# ATmega328_-_nRF24L01p_test_board.net
KiCad netlist of a schematic drawn in EAGLE
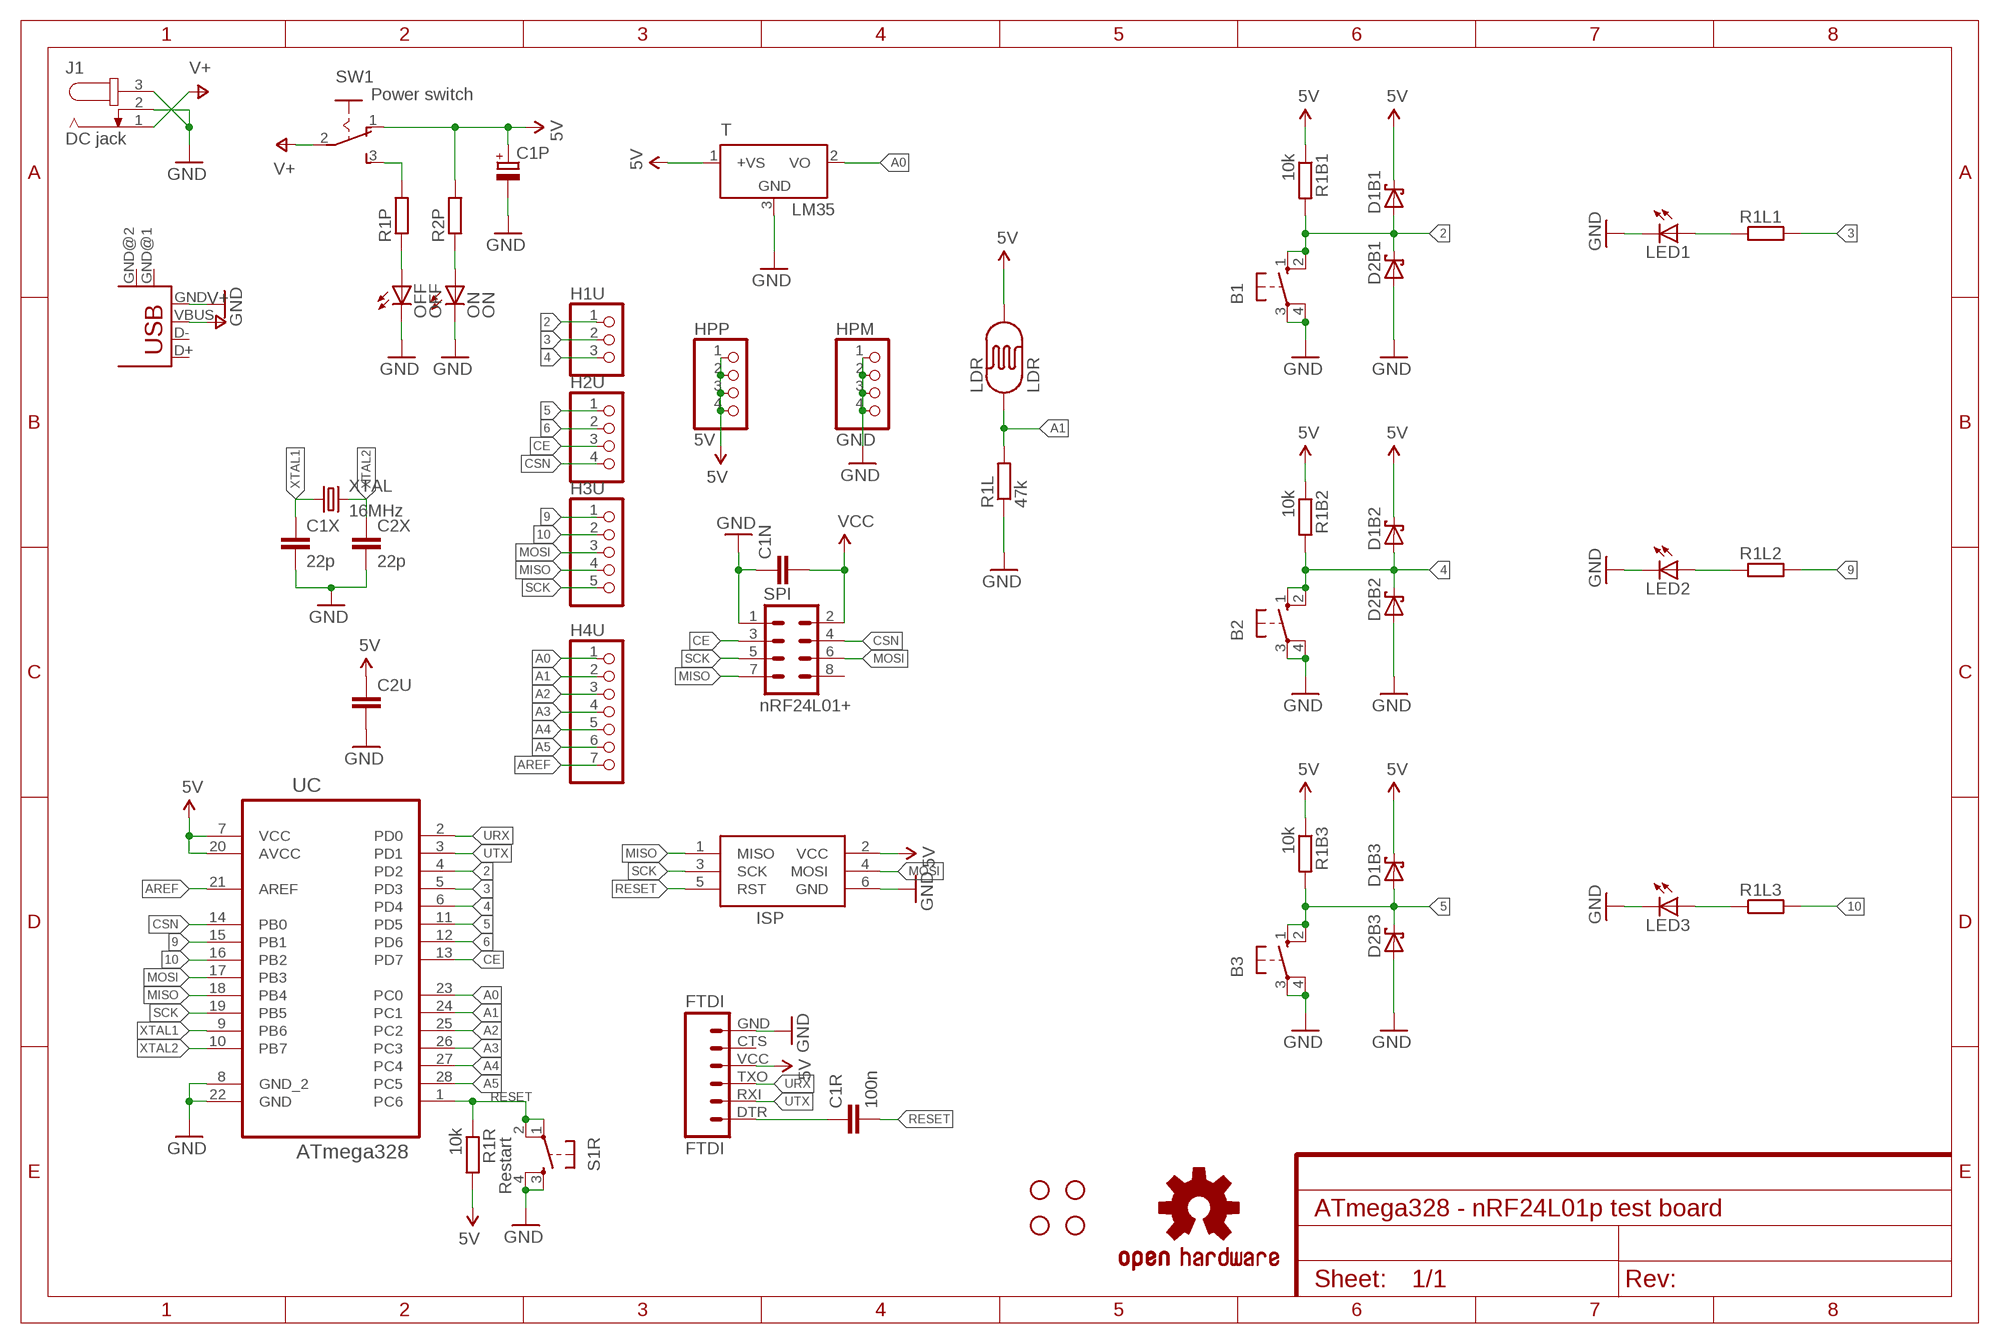
[diagram p0: schematic, sheet 1]

(export (version "E")
  (design (tool "Eeschema 10.0.6"))
  (components
    (comp (ref "B1")
      (value "40-XX")
      (footprint "eagle-import:B3F-40XX")
      (fields (field (name "MF") "OMRON COMPONENTS USA") (field (name "MPN") "B3F-4000"))
      (libsource (lib "eagle-import") (part "40-XX"))
    )
    (comp (ref "B2")
      (value "40-XX")
      (footprint "eagle-import:B3F-40XX")
      (fields (field (name "MF") "OMRON COMPONENTS USA") (field (name "MPN") "B3F-4000"))
      (libsource (lib "eagle-import") (part "40-XX"))
    )
    (comp (ref "B3")
      (value "40-XX")
      (footprint "eagle-import:B3F-40XX")
      (fields (field (name "MF") "OMRON COMPONENTS USA") (field (name "MPN") "B3F-4000"))
      (libsource (lib "eagle-import") (part "40-XX"))
    )
    (comp (ref "C1N")
      (value "C-EU050-025X075")
      (footprint "eagle-import:C050-025X075")
      (libsource (lib "eagle-import") (part "resistor_C-EU050-025X075"))
    )
    (comp (ref "C1P")
      (value "CPOL-EUE5-8.5")
      (footprint "eagle-import:E5-8,5")
      (libsource (lib "eagle-import") (part "CPOL-EUE5-8.5"))
    )
    (comp (ref "C1R")
      (value "100n")
      (footprint "eagle-import:C050-025X075")
      (libsource (lib "eagle-import") (part "resistor_C-EU050-025X075"))
    )
    (comp (ref "C1X")
      (value "22p")
      (footprint "eagle-import:C025-025X050")
      (libsource (lib "eagle-import") (part "resistor_C-EU025-025X050"))
    )
    (comp (ref "C2U")
      (value "C-EU050-055X075")
      (footprint "eagle-import:C050-055X075")
      (libsource (lib "eagle-import") (part "C-EU050-055X075"))
    )
    (comp (ref "C2X")
      (value "22p")
      (footprint "eagle-import:C025-025X050")
      (libsource (lib "eagle-import") (part "resistor_C-EU025-025X050"))
    )
    (comp (ref "D1B1")
      (value "SCHOTTKY-DIODEDO41-7")
      (footprint "eagle-import:DO41-7")
      (libsource (lib "eagle-import") (part "SCHOTTKY-DIODEDO41-7"))
    )
    (comp (ref "D1B2")
      (value "SCHOTTKY-DIODEDO41-7")
      (footprint "eagle-import:DO41-7")
      (libsource (lib "eagle-import") (part "SCHOTTKY-DIODEDO41-7"))
    )
    (comp (ref "D1B3")
      (value "SCHOTTKY-DIODEDO41-7")
      (footprint "eagle-import:DO41-7")
      (libsource (lib "eagle-import") (part "SCHOTTKY-DIODEDO41-7"))
    )
    (comp (ref "D2B1")
      (value "SCHOTTKY-DIODEDO41-7")
      (footprint "eagle-import:DO41-7")
      (libsource (lib "eagle-import") (part "SCHOTTKY-DIODEDO41-7"))
    )
    (comp (ref "D2B2")
      (value "SCHOTTKY-DIODEDO41-7")
      (footprint "eagle-import:DO41-7")
      (libsource (lib "eagle-import") (part "SCHOTTKY-DIODEDO41-7"))
    )
    (comp (ref "D2B3")
      (value "SCHOTTKY-DIODEDO41-7")
      (footprint "eagle-import:DO41-7")
      (libsource (lib "eagle-import") (part "SCHOTTKY-DIODEDO41-7"))
    )
    (comp (ref "FTDI")
      (value "FTDI")
      (footprint "eagle-import:FTDI_BASIC")
      (libsource (lib "eagle-import") (part "FTDI_BASICPTH"))
    )
    (comp (ref "H1")
      (value "STAND-OFF")
      (footprint "eagle-import:STAND-OFF")
      (libsource (lib "eagle-import") (part "STAND-OFF"))
    )
    (comp (ref "H1U")
      (value "PINHD-1X3")
      (footprint "eagle-import:1X03")
      (libsource (lib "eagle-import") (part "PINHD-1X3"))
    )
    (comp (ref "H2")
      (value "STAND-OFF")
      (footprint "eagle-import:STAND-OFF")
      (libsource (lib "eagle-import") (part "STAND-OFF"))
    )
    (comp (ref "H2U")
      (value "PINHD-1X4")
      (footprint "eagle-import:1X04")
      (libsource (lib "eagle-import") (part "PINHD-1X4"))
    )
    (comp (ref "H3")
      (value "STAND-OFF")
      (footprint "eagle-import:STAND-OFF")
      (libsource (lib "eagle-import") (part "STAND-OFF"))
    )
    (comp (ref "H3U")
      (value "PINHD-1X5")
      (footprint "eagle-import:1X05")
      (libsource (lib "eagle-import") (part "PINHD-1X5"))
    )
    (comp (ref "H4")
      (value "STAND-OFF")
      (footprint "eagle-import:STAND-OFF")
      (libsource (lib "eagle-import") (part "STAND-OFF"))
    )
    (comp (ref "H4U")
      (value "PINHD-1X7")
      (footprint "eagle-import:1X07")
      (libsource (lib "eagle-import") (part "PINHD-1X7"))
    )
    (comp (ref "HPM")
      (value "GND")
      (footprint "eagle-import:1X04")
      (libsource (lib "eagle-import") (part "PINHD-1X4"))
    )
    (comp (ref "HPP")
      (value "5V")
      (footprint "eagle-import:1X04")
      (libsource (lib "eagle-import") (part "PINHD-1X4"))
    )
    (comp (ref "ISP")
      (value "AVRISP-6")
      (footprint "eagle-import:AVRISP")
      (libsource (lib "eagle-import") (part "AVRISP-6"))
    )
    (comp (ref "J1")
      (value "DC jack")
      (footprint "eagle-import:SPC4078")
      (libsource (lib "eagle-import") (part "JACK-PLUG1"))
    )
    (comp (ref "J2")
      (value "USB mini")
      (footprint "eagle-import:USB-MB-H")
      (libsource (lib "eagle-import") (part "USB-MB-H"))
    )
    (comp (ref "LDR")
      (value "LDR")
      (footprint "eagle-import:PHOTOCELL")
      (libsource (lib "eagle-import") (part "PHOTOCELLPTH"))
    )
    (comp (ref "LED1")
      (value "LED5MM")
      (footprint "eagle-import:LED5MM")
      (libsource (lib "eagle-import") (part "LED5MM"))
    )
    (comp (ref "LED2")
      (value "LED5MM")
      (footprint "eagle-import:LED5MM")
      (libsource (lib "eagle-import") (part "LED5MM"))
    )
    (comp (ref "LED3")
      (value "LED5MM")
      (footprint "eagle-import:LED5MM")
      (libsource (lib "eagle-import") (part "LED5MM"))
    )
    (comp (ref "LOGO1")
      (value "OSHW-LOGOM-COPPER")
      (footprint "eagle-import:OSHW-LOGO-M_COPPER")
      (libsource (lib "eagle-import") (part "OSHW-LOGOM-COPPER"))
    )
    (comp (ref "OFF")
      (value "OFF")
      (footprint "eagle-import:LED3MM")
      (libsource (lib "eagle-import") (part "LED3MM"))
    )
    (comp (ref "ON")
      (value "ON")
      (footprint "eagle-import:LED3MM")
      (libsource (lib "eagle-import") (part "LED3MM"))
    )
    (comp (ref "R1B1")
      (value "10k")
      (footprint "eagle-import:0207_7")
      (libsource (lib "eagle-import") (part "R-EU_0207/7"))
    )
    (comp (ref "R1B2")
      (value "10k")
      (footprint "eagle-import:0207_7")
      (libsource (lib "eagle-import") (part "R-EU_0207/7"))
    )
    (comp (ref "R1B3")
      (value "10k")
      (footprint "eagle-import:0207_7")
      (libsource (lib "eagle-import") (part "R-EU_0207/7"))
    )
    (comp (ref "R1L")
      (value "47k")
      (footprint "eagle-import:0207_7")
      (libsource (lib "eagle-import") (part "R-EU_0207/7"))
    )
    (comp (ref "R1L1")
      (value "R-EU_0207/7")
      (footprint "eagle-import:0207_7")
      (libsource (lib "eagle-import") (part "R-EU_0207/7"))
    )
    (comp (ref "R1L2")
      (value "R-EU_0207/7")
      (footprint "eagle-import:0207_7")
      (libsource (lib "eagle-import") (part "R-EU_0207/7"))
    )
    (comp (ref "R1L3")
      (value "R-EU_0207/7")
      (footprint "eagle-import:0207_7")
      (libsource (lib "eagle-import") (part "R-EU_0207/7"))
    )
    (comp (ref "R1P")
      (value "R-EU_0207/7")
      (footprint "eagle-import:0207_7")
      (libsource (lib "eagle-import") (part "R-EU_0207/7"))
    )
    (comp (ref "R1R")
      (value "10k")
      (footprint "eagle-import:0207_7")
      (libsource (lib "eagle-import") (part "R-EU_0207/7"))
    )
    (comp (ref "R2P")
      (value "R-EU_0207/7")
      (footprint "eagle-import:0207_7")
      (libsource (lib "eagle-import") (part "R-EU_0207/7"))
    )
    (comp (ref "S1R")
      (value "Restart")
      (footprint "eagle-import:TACTILE-PTH")
      (libsource (lib "eagle-import") (part "TAC_SWITCHPTH"))
    )
    (comp (ref "SPI")
      (value "nRF24L01+")
      (footprint "eagle-import:2X4")
      (fields (field (name "MF") "OLIMEX") (field (name "MPN") "MOD-NRF24LR"))
      (libsource (lib "eagle-import") (part "M04X2"))
    )
    (comp (ref "SW1")
      (value "Power switch")
      (footprint "eagle-import:SWITCH_2MM")
      (libsource (lib "eagle-import") (part "SPDT_SWITCH_2MM"))
    )
    (comp (ref "T")
      (value "LM35")
      (footprint "eagle-import:TO92")
      (libsource (lib "eagle-import") (part "LM35CZ"))
    )
    (comp (ref "UC")
      (value "ATmega328")
      (footprint "eagle-import:DIP254P762X457-28")
      (fields (field (name "MPN") "ATMEGA328P-PU"))
      (libsource (lib "eagle-import") (part "ATMEGA328P-PU"))
    )
    (comp (ref "XTAL")
      (value "16MHz")
      (footprint "eagle-import:HC49_S")
      (libsource (lib "eagle-import") (part "CRYSTALHC49S"))
    )
  )
  (nets
    (net (code "1") (name "2") (class "Default")
      (node (ref "B1") (pin "1") (pinfunction "S_1") (pintype "passive"))
      (node (ref "B1") (pin "2") (pinfunction "S1_2") (pintype "passive"))
      (node (ref "D1B1") (pin "A") (pinfunction "A_A") (pintype "passive"))
      (node (ref "D2B1") (pin "C") (pinfunction "C_C") (pintype "passive"))
      (node (ref "H1U") (pin "1") (pinfunction "1_1") (pintype "passive"))
      (node (ref "R1B1") (pin "2") (pinfunction "2_2") (pintype "passive"))
      (node (ref "UC") (pin "4") (pinfunction "PD2_4") (pintype "bidirectional"))
    )
    (net (code "2") (name "3") (class "Default")
      (node (ref "H1U") (pin "2") (pinfunction "2_2") (pintype "passive"))
      (node (ref "R1L1") (pin "2") (pinfunction "2_2") (pintype "passive"))
      (node (ref "UC") (pin "5") (pinfunction "PD3_5") (pintype "bidirectional"))
    )
    (net (code "3") (name "4") (class "Default")
      (node (ref "B2") (pin "1") (pinfunction "S_1") (pintype "passive"))
      (node (ref "B2") (pin "2") (pinfunction "S1_2") (pintype "passive"))
      (node (ref "D1B2") (pin "A") (pinfunction "A_A") (pintype "passive"))
      (node (ref "D2B2") (pin "C") (pinfunction "C_C") (pintype "passive"))
      (node (ref "H1U") (pin "3") (pinfunction "3_3") (pintype "passive"))
      (node (ref "R1B2") (pin "2") (pinfunction "2_2") (pintype "passive"))
      (node (ref "UC") (pin "6") (pinfunction "PD4_6") (pintype "bidirectional"))
    )
    (net (code "4") (name "5") (class "Default")
      (node (ref "B3") (pin "1") (pinfunction "S_1") (pintype "passive"))
      (node (ref "B3") (pin "2") (pinfunction "S1_2") (pintype "passive"))
      (node (ref "D1B3") (pin "A") (pinfunction "A_A") (pintype "passive"))
      (node (ref "D2B3") (pin "C") (pinfunction "C_C") (pintype "passive"))
      (node (ref "H2U") (pin "1") (pinfunction "1_1") (pintype "passive"))
      (node (ref "R1B3") (pin "2") (pinfunction "2_2") (pintype "passive"))
      (node (ref "UC") (pin "11") (pinfunction "PD5_11") (pintype "bidirectional"))
    )
    (net (code "5") (name "5V") (class "Default")
      (node (ref "C1P") (pin "+") (pinfunction "+_+") (pintype "passive"))
      (node (ref "C2U") (pin "1") (pinfunction "1_1") (pintype "passive"))
      (node (ref "D1B1") (pin "C") (pinfunction "C_C") (pintype "passive"))
      (node (ref "D1B2") (pin "C") (pinfunction "C_C") (pintype "passive"))
      (node (ref "D1B3") (pin "C") (pinfunction "C_C") (pintype "passive"))
      (node (ref "FTDI") (pin "VCC") (pinfunction "4_VCC") (pintype "passive"))
      (node (ref "HPP") (pin "1") (pinfunction "1_1") (pintype "passive"))
      (node (ref "HPP") (pin "2") (pinfunction "2_2") (pintype "passive"))
      (node (ref "HPP") (pin "3") (pinfunction "3_3") (pintype "passive"))
      (node (ref "HPP") (pin "4") (pinfunction "4_4") (pintype "passive"))
      (node (ref "ISP") (pin "2") (pinfunction "VCC_2") (pintype "power_in"))
      (node (ref "LDR") (pin "2") (pinfunction "P$2_2") (pintype "bidirectional"))
      (node (ref "R1B1") (pin "1") (pinfunction "1_1") (pintype "passive"))
      (node (ref "R1B2") (pin "1") (pinfunction "1_1") (pintype "passive"))
      (node (ref "R1B3") (pin "1") (pinfunction "1_1") (pintype "passive"))
      (node (ref "R1R") (pin "2") (pinfunction "2_2") (pintype "passive"))
      (node (ref "R2P") (pin "2") (pinfunction "2_2") (pintype "passive"))
      (node (ref "SW1") (pin "1") (pinfunction "1_1") (pintype "passive"))
      (node (ref "T") (pin "1") (pinfunction "+VS_1") (pintype "input"))
      (node (ref "UC") (pin "20") (pinfunction "AVCC_20") (pintype "power_in"))
      (node (ref "UC") (pin "7") (pinfunction "VCC_7") (pintype "power_in"))
    )
    (net (code "6") (name "6") (class "Default")
      (node (ref "H2U") (pin "2") (pinfunction "2_2") (pintype "passive"))
      (node (ref "UC") (pin "12") (pinfunction "PD6_12") (pintype "bidirectional"))
    )
    (net (code "7") (name "9") (class "Default")
      (node (ref "H3U") (pin "1") (pinfunction "1_1") (pintype "passive"))
      (node (ref "R1L2") (pin "2") (pinfunction "2_2") (pintype "passive"))
      (node (ref "UC") (pin "15") (pinfunction "PB1_15") (pintype "bidirectional"))
    )
    (net (code "8") (name "10") (class "Default")
      (node (ref "H3U") (pin "2") (pinfunction "2_2") (pintype "passive"))
      (node (ref "R1L3") (pin "2") (pinfunction "2_2") (pintype "passive"))
      (node (ref "UC") (pin "16") (pinfunction "PB2_16") (pintype "bidirectional"))
    )
    (net (code "9") (name "A0") (class "Default")
      (node (ref "H4U") (pin "1") (pinfunction "1_1") (pintype "passive"))
      (node (ref "T") (pin "2") (pinfunction "VO_2") (pintype "input"))
      (node (ref "UC") (pin "23") (pinfunction "PC0_23") (pintype "bidirectional"))
    )
    (net (code "10") (name "A1") (class "Default")
      (node (ref "H4U") (pin "2") (pinfunction "2_2") (pintype "passive"))
      (node (ref "LDR") (pin "1") (pinfunction "P$1_1") (pintype "bidirectional"))
      (node (ref "R1L") (pin "2") (pinfunction "2_2") (pintype "passive"))
      (node (ref "UC") (pin "24") (pinfunction "PC1_24") (pintype "bidirectional"))
    )
    (net (code "11") (name "A2") (class "Default")
      (node (ref "H4U") (pin "3") (pinfunction "3_3") (pintype "passive"))
      (node (ref "UC") (pin "25") (pinfunction "PC2_25") (pintype "bidirectional"))
    )
    (net (code "12") (name "A3") (class "Default")
      (node (ref "H4U") (pin "4") (pinfunction "4_4") (pintype "passive"))
      (node (ref "UC") (pin "26") (pinfunction "PC3_26") (pintype "bidirectional"))
    )
    (net (code "13") (name "A4") (class "Default")
      (node (ref "H4U") (pin "5") (pinfunction "5_5") (pintype "passive"))
      (node (ref "UC") (pin "27") (pinfunction "PC4_27") (pintype "bidirectional"))
    )
    (net (code "14") (name "A5") (class "Default")
      (node (ref "H4U") (pin "6") (pinfunction "6_6") (pintype "passive"))
      (node (ref "UC") (pin "28") (pinfunction "PC5_28") (pintype "bidirectional"))
    )
    (net (code "15") (name "AREF") (class "Default")
      (node (ref "H4U") (pin "7") (pinfunction "7_7") (pintype "passive"))
      (node (ref "UC") (pin "21") (pinfunction "AREF_21") (pintype "input"))
    )
    (net (code "16") (name "CE") (class "Default")
      (node (ref "H2U") (pin "3") (pinfunction "3_3") (pintype "passive"))
      (node (ref "SPI") (pin "3") (pinfunction "3_3") (pintype "passive"))
      (node (ref "UC") (pin "13") (pinfunction "PD7_13") (pintype "bidirectional"))
    )
    (net (code "17") (name "CSN") (class "Default")
      (node (ref "H2U") (pin "4") (pinfunction "4_4") (pintype "passive"))
      (node (ref "SPI") (pin "4") (pinfunction "4_4") (pintype "passive"))
      (node (ref "UC") (pin "14") (pinfunction "PB0_14") (pintype "bidirectional"))
    )
    (net (code "18") (name "GND") (class "Default")
      (node (ref "B1") (pin "3") (pinfunction "P_3") (pintype "passive"))
      (node (ref "B1") (pin "4") (pinfunction "P1_4") (pintype "passive"))
      (node (ref "B2") (pin "3") (pinfunction "P_3") (pintype "passive"))
      (node (ref "B2") (pin "4") (pinfunction "P1_4") (pintype "passive"))
      (node (ref "B3") (pin "3") (pinfunction "P_3") (pintype "passive"))
      (node (ref "B3") (pin "4") (pinfunction "P1_4") (pintype "passive"))
      (node (ref "C1N") (pin "1") (pinfunction "1_1") (pintype "passive"))
      (node (ref "C1P") (pin "-") (pinfunction "-_-") (pintype "passive"))
      (node (ref "C1X") (pin "2") (pinfunction "2_2") (pintype "passive"))
      (node (ref "C2U") (pin "2") (pinfunction "2_2") (pintype "passive"))
      (node (ref "C2X") (pin "2") (pinfunction "2_2") (pintype "passive"))
      (node (ref "D2B1") (pin "A") (pinfunction "A_A") (pintype "passive"))
      (node (ref "D2B2") (pin "A") (pinfunction "A_A") (pintype "passive"))
      (node (ref "D2B3") (pin "A") (pinfunction "A_A") (pintype "passive"))
      (node (ref "FTDI") (pin "GND") (pinfunction "6_GND") (pintype "passive"))
      (node (ref "HPM") (pin "1") (pinfunction "1_1") (pintype "passive"))
      (node (ref "HPM") (pin "2") (pinfunction "2_2") (pintype "passive"))
      (node (ref "HPM") (pin "3") (pinfunction "3_3") (pintype "passive"))
      (node (ref "HPM") (pin "4") (pinfunction "4_4") (pintype "passive"))
      (node (ref "ISP") (pin "6") (pinfunction "GND_6") (pintype "power_in"))
      (node (ref "J1") (pin "2") (pinfunction "2_2") (pintype "passive"))
      (node (ref "J1") (pin "3") (pinfunction "3_3") (pintype "passive"))
      (node (ref "J2") (pin "GND") (pinfunction "GND_GND") (pintype "bidirectional"))
      (node (ref "LED1") (pin "K") (pinfunction "C_K") (pintype "passive"))
      (node (ref "LED2") (pin "K") (pinfunction "C_K") (pintype "passive"))
      (node (ref "LED3") (pin "K") (pinfunction "C_K") (pintype "passive"))
      (node (ref "OFF") (pin "K") (pinfunction "C_K") (pintype "passive"))
      (node (ref "ON") (pin "K") (pinfunction "C_K") (pintype "passive"))
      (node (ref "R1L") (pin "1") (pinfunction "1_1") (pintype "passive"))
      (node (ref "S1R") (pin "3") (pinfunction "3_3") (pintype "passive"))
      (node (ref "S1R") (pin "4") (pinfunction "4_4") (pintype "passive"))
      (node (ref "SPI") (pin "1") (pinfunction "1_1") (pintype "passive"))
      (node (ref "T") (pin "3") (pinfunction "GND_3") (pintype "power_in"))
      (node (ref "UC") (pin "22") (pinfunction "GND_22") (pintype "passive"))
      (node (ref "UC") (pin "8") (pinfunction "GND_2_8") (pintype "passive"))
    )
    (net (code "19") (name "MISO") (class "Default")
      (node (ref "H3U") (pin "4") (pinfunction "4_4") (pintype "passive"))
      (node (ref "ISP") (pin "1") (pinfunction "MISO_1") (pintype "input"))
      (node (ref "SPI") (pin "7") (pinfunction "7_7") (pintype "passive"))
      (node (ref "UC") (pin "18") (pinfunction "PB4_18") (pintype "bidirectional"))
    )
    (net (code "20") (name "MOSI") (class "Default")
      (node (ref "H3U") (pin "3") (pinfunction "3_3") (pintype "passive"))
      (node (ref "ISP") (pin "4") (pinfunction "MOSI_4") (pintype "output"))
      (node (ref "SPI") (pin "6") (pinfunction "6_6") (pintype "passive"))
      (node (ref "UC") (pin "17") (pinfunction "PB3_17") (pintype "bidirectional"))
    )
    (net (code "21") (name "Net-(FTDI-1)") (class "Default")
      (node (ref "C1R") (pin "1") (pinfunction "1_1") (pintype "passive"))
      (node (ref "FTDI") (pin "DTR") (pinfunction "1_DTR") (pintype "passive"))
    )
    (net (code "22") (name "Net-(LED1-PadA)") (class "Default")
      (node (ref "LED1") (pin "A") (pinfunction "A_A") (pintype "passive"))
      (node (ref "R1L1") (pin "1") (pinfunction "1_1") (pintype "passive"))
    )
    (net (code "23") (name "Net-(LED2-PadA)") (class "Default")
      (node (ref "LED2") (pin "A") (pinfunction "A_A") (pintype "passive"))
      (node (ref "R1L2") (pin "1") (pinfunction "1_1") (pintype "passive"))
    )
    (net (code "24") (name "Net-(LED3-PadA)") (class "Default")
      (node (ref "LED3") (pin "A") (pinfunction "A_A") (pintype "passive"))
      (node (ref "R1L3") (pin "1") (pinfunction "1_1") (pintype "passive"))
    )
    (net (code "25") (name "Net-(OFF-PadA)") (class "Default")
      (node (ref "OFF") (pin "A") (pinfunction "A_A") (pintype "passive"))
      (node (ref "R1P") (pin "1") (pinfunction "1_1") (pintype "passive"))
    )
    (net (code "26") (name "Net-(ON-PadA)") (class "Default")
      (node (ref "ON") (pin "A") (pinfunction "A_A") (pintype "passive"))
      (node (ref "R2P") (pin "1") (pinfunction "1_1") (pintype "passive"))
    )
    (net (code "27") (name "Net-(R1P-Pad2)") (class "Default")
      (node (ref "R1P") (pin "2") (pinfunction "2_2") (pintype "passive"))
      (node (ref "SW1") (pin "3") (pinfunction "3_3") (pintype "passive"))
    )
    (net (code "28") (name "RESET") (class "Default")
      (node (ref "C1R") (pin "2") (pinfunction "2_2") (pintype "passive"))
      (node (ref "ISP") (pin "5") (pinfunction "RST_5") (pintype "output"))
      (node (ref "R1R") (pin "1") (pinfunction "1_1") (pintype "passive"))
      (node (ref "S1R") (pin "1") (pinfunction "1_1") (pintype "passive"))
      (node (ref "S1R") (pin "2") (pinfunction "2_2") (pintype "passive"))
      (node (ref "UC") (pin "1") (pinfunction "PC6_1") (pintype "bidirectional"))
    )
    (net (code "29") (name "SCK") (class "Default")
      (node (ref "H3U") (pin "5") (pinfunction "5_5") (pintype "passive"))
      (node (ref "ISP") (pin "3") (pinfunction "SCK_3") (pintype "output"))
      (node (ref "SPI") (pin "5") (pinfunction "5_5") (pintype "passive"))
      (node (ref "UC") (pin "19") (pinfunction "PB5_19") (pintype "bidirectional"))
    )
    (net (code "30") (name "URX") (class "Default")
      (node (ref "FTDI") (pin "TXO") (pinfunction "3_TXO") (pintype "passive"))
      (node (ref "UC") (pin "2") (pinfunction "PD0_2") (pintype "bidirectional"))
    )
    (net (code "31") (name "UTX") (class "Default")
      (node (ref "FTDI") (pin "RXI") (pinfunction "2_RXI") (pintype "passive"))
      (node (ref "UC") (pin "3") (pinfunction "PD1_3") (pintype "bidirectional"))
    )
    (net (code "32") (name "V+") (class "Default")
      (node (ref "J1") (pin "1") (pinfunction "1_1") (pintype "passive"))
      (node (ref "J2") (pin "VBUS") (pinfunction "VBUS_VBUS") (pintype "bidirectional"))
      (node (ref "SW1") (pin "2") (pinfunction "2_2") (pintype "passive"))
    )
    (net (code "33") (name "VCC") (class "Default")
      (node (ref "C1N") (pin "2") (pinfunction "2_2") (pintype "passive"))
      (node (ref "SPI") (pin "2") (pinfunction "2_2") (pintype "passive"))
    )
    (net (code "34") (name "XTAL1") (class "Default")
      (node (ref "C1X") (pin "1") (pinfunction "1_1") (pintype "passive"))
      (node (ref "UC") (pin "9") (pinfunction "PB6_9") (pintype "bidirectional"))
      (node (ref "XTAL") (pin "1") (pinfunction "1_1") (pintype "passive"))
    )
    (net (code "35") (name "XTAL2") (class "Default")
      (node (ref "C2X") (pin "1") (pinfunction "1_1") (pintype "passive"))
      (node (ref "UC") (pin "10") (pinfunction "PB7_10") (pintype "bidirectional"))
      (node (ref "XTAL") (pin "2") (pinfunction "2_2") (pintype "passive"))
    )
    (net (code "36") (name "unconnected-(FTDI-5-PadCTS)") (class "Default")
      (node (ref "FTDI") (pin "CTS") (pinfunction "5_CTS") (pintype "passive"))
    )
    (net (code "37") (name "unconnected-(J2-GND-PadGND@1)") (class "Default")
      (node (ref "J2") (pin "GND@1") (pinfunction "GND_GND@1") (pintype "bidirectional"))
    )
    (net (code "38") (name "unconnected-(J2-GND-PadGND@2)") (class "Default")
      (node (ref "J2") (pin "GND@2") (pinfunction "GND_GND@2") (pintype "bidirectional"))
    )
    (net (code "39") (name "unconnected-(J2-PadD+)") (class "Default")
      (node (ref "J2") (pin "D+") (pinfunction "D+_D+") (pintype "bidirectional"))
    )
    (net (code "40") (name "unconnected-(J2-PadD-)") (class "Default")
      (node (ref "J2") (pin "D-") (pinfunction "D-_D-") (pintype "bidirectional"))
    )
    (net (code "41") (name "unconnected-(SPI-Pad8)") (class "Default")
      (node (ref "SPI") (pin "8") (pinfunction "8_8") (pintype "passive"))
    )
  )
)
